# Placa_Final.net
KiCad netlist of a schematic drawn in EAGLE
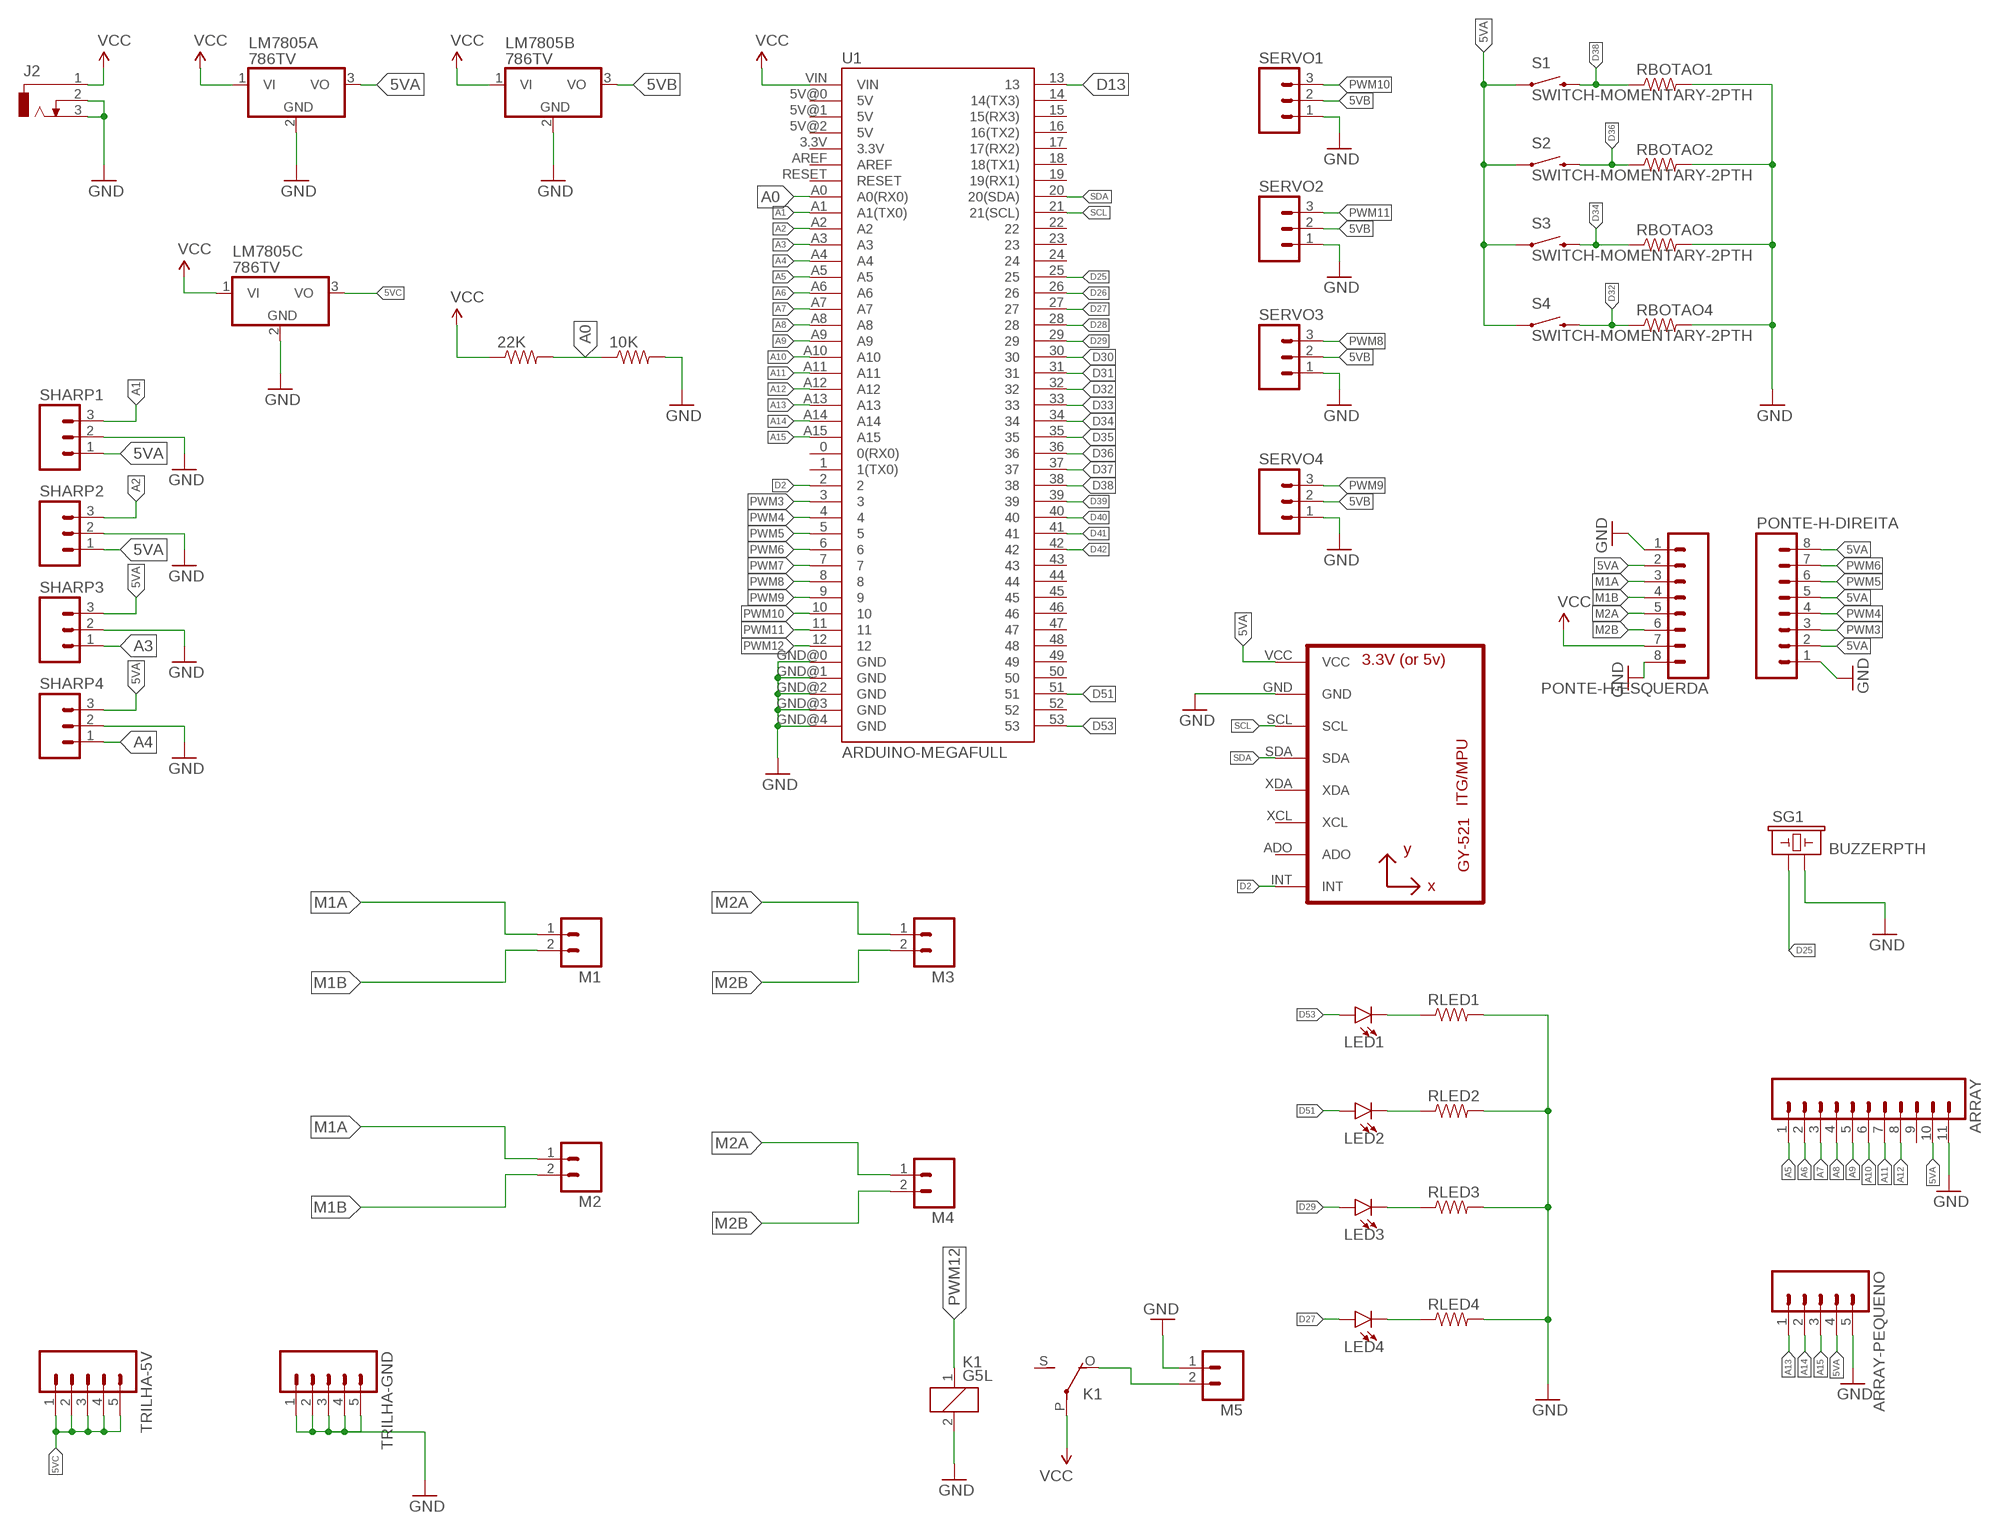
[diagram p0: schematic, sheet 1]
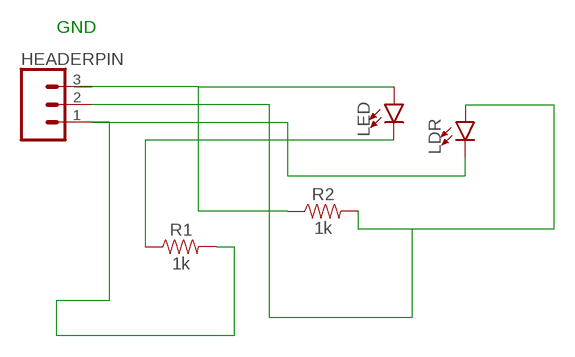
[diagram p1: schematic, sheet 2]
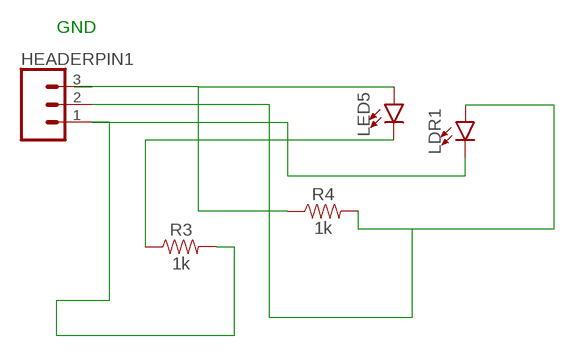
[diagram p2: schematic, sheet 3]
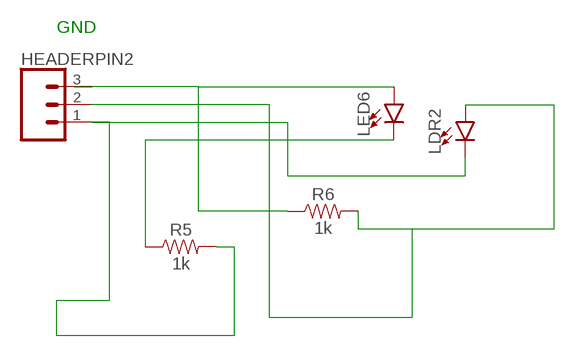
[diagram p3: schematic, sheet 4]
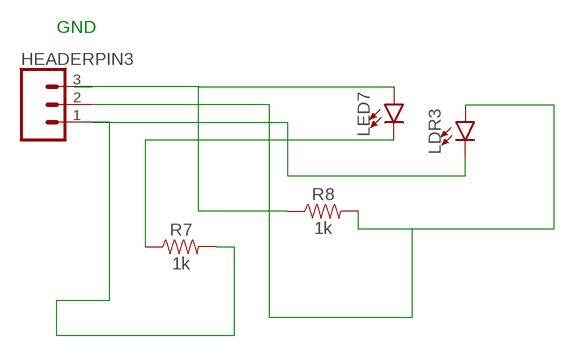
[diagram p4: schematic, sheet 5]
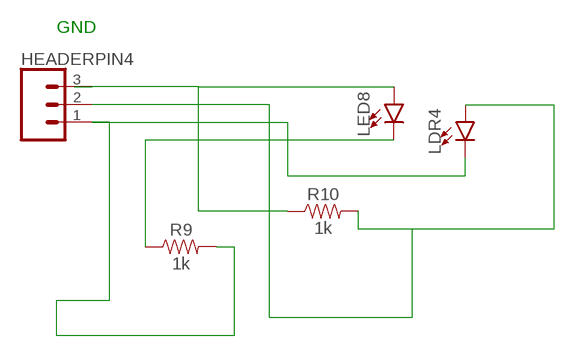
[diagram p5: schematic, sheet 6]
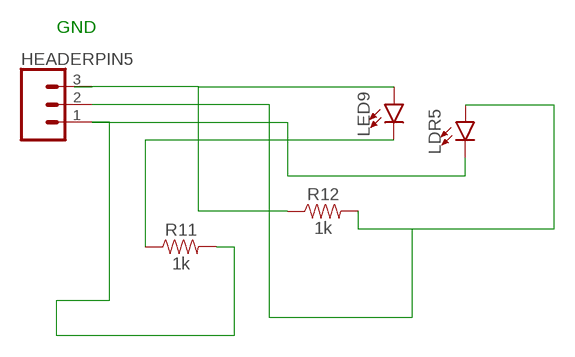
[diagram p6: schematic, sheet 7]
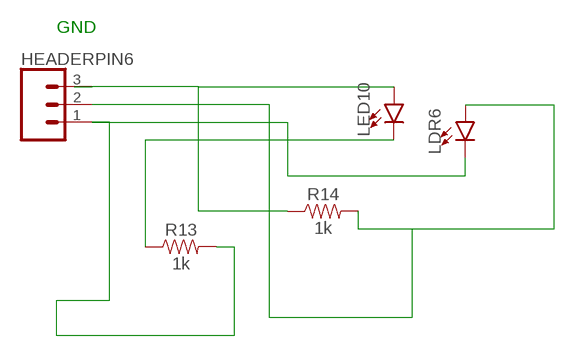
[diagram p7: schematic, sheet 8]
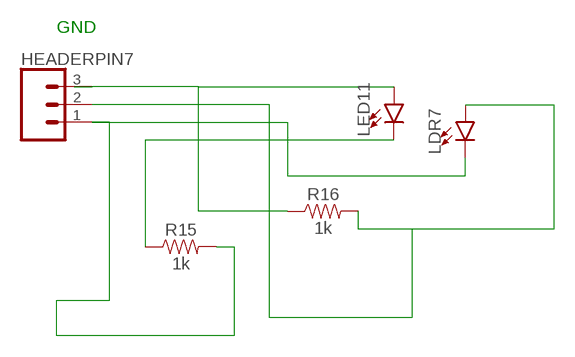
[diagram p8: schematic, sheet 9]
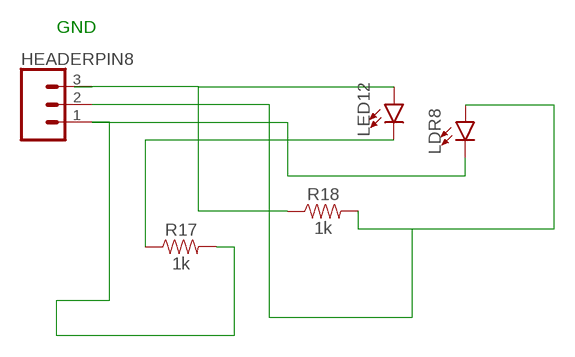
[diagram p9: schematic, sheet 10]

(export (version "E")
  (design (tool "Eeschema 10.0.6"))
  (components
    (comp (ref "HEADERPIN5")
      (value "CONN_03")
      (footprint "eagle-import:1X03")
      (libsource (lib "eagle-import") (part "CONN_03"))
    )
    (comp (ref "LDR5")
      (value "LED5MM")
      (footprint "eagle-import:LED_5MM")
      (libsource (lib "eagle-import") (part "LED5MM"))
    )
    (comp (ref "LED9")
      (value "LED5MM")
      (footprint "eagle-import:LED_5MM")
      (libsource (lib "eagle-import") (part "LED5MM"))
    )
    (comp (ref "R11")
      (value "1k")
      (footprint "eagle-import:AXIAL-0.3")
      (libsource (lib "eagle-import") (part "1KOHM-HORIZ-1/4W-5%"))
    )
    (comp (ref "R12")
      (value "1k")
      (footprint "eagle-import:AXIAL-0.3")
      (libsource (lib "eagle-import") (part "1KOHM-HORIZ-1/4W-5%"))
    )
    (comp (ref "HEADERPIN2")
      (value "CONN_03")
      (footprint "eagle-import:1X03")
      (libsource (lib "eagle-import") (part "CONN_03"))
    )
    (comp (ref "LDR2")
      (value "LED5MM")
      (footprint "eagle-import:LED_5MM")
      (libsource (lib "eagle-import") (part "LED5MM"))
    )
    (comp (ref "LED6")
      (value "LED5MM")
      (footprint "eagle-import:LED_5MM")
      (libsource (lib "eagle-import") (part "LED5MM"))
    )
    (comp (ref "R5")
      (value "1k")
      (footprint "eagle-import:AXIAL-0.3")
      (libsource (lib "eagle-import") (part "1KOHM-HORIZ-1/4W-5%"))
    )
    (comp (ref "R6")
      (value "1k")
      (footprint "eagle-import:AXIAL-0.3")
      (libsource (lib "eagle-import") (part "1KOHM-HORIZ-1/4W-5%"))
    )
    (comp (ref "HEADERPIN")
      (value "CONN_03")
      (footprint "eagle-import:1X03")
      (libsource (lib "eagle-import") (part "CONN_03"))
    )
    (comp (ref "LDR")
      (value "LED5MM")
      (footprint "eagle-import:LED_5MM")
      (libsource (lib "eagle-import") (part "LED5MM"))
    )
    (comp (ref "LED")
      (value "LED5MM")
      (footprint "eagle-import:LED_5MM")
      (libsource (lib "eagle-import") (part "LED5MM"))
    )
    (comp (ref "R1")
      (value "1k")
      (footprint "eagle-import:AXIAL-0.3")
      (libsource (lib "eagle-import") (part "1KOHM-HORIZ-1/4W-5%"))
    )
    (comp (ref "R2")
      (value "1k")
      (footprint "eagle-import:AXIAL-0.3")
      (libsource (lib "eagle-import") (part "1KOHM-HORIZ-1/4W-5%"))
    )
    (comp (ref "HEADERPIN3")
      (value "CONN_03")
      (footprint "eagle-import:1X03")
      (libsource (lib "eagle-import") (part "CONN_03"))
    )
    (comp (ref "LDR3")
      (value "LED5MM")
      (footprint "eagle-import:LED_5MM")
      (libsource (lib "eagle-import") (part "LED5MM"))
    )
    (comp (ref "LED7")
      (value "LED5MM")
      (footprint "eagle-import:LED_5MM")
      (libsource (lib "eagle-import") (part "LED5MM"))
    )
    (comp (ref "R7")
      (value "1k")
      (footprint "eagle-import:AXIAL-0.3")
      (libsource (lib "eagle-import") (part "1KOHM-HORIZ-1/4W-5%"))
    )
    (comp (ref "R8")
      (value "1k")
      (footprint "eagle-import:AXIAL-0.3")
      (libsource (lib "eagle-import") (part "1KOHM-HORIZ-1/4W-5%"))
    )
    (comp (ref "HEADERPIN8")
      (value "CONN_03")
      (footprint "eagle-import:1X03")
      (libsource (lib "eagle-import") (part "CONN_03"))
    )
    (comp (ref "LDR8")
      (value "LED5MM")
      (footprint "eagle-import:LED_5MM")
      (libsource (lib "eagle-import") (part "LED5MM"))
    )
    (comp (ref "LED12")
      (value "LED5MM")
      (footprint "eagle-import:LED_5MM")
      (libsource (lib "eagle-import") (part "LED5MM"))
    )
    (comp (ref "R17")
      (value "1k")
      (footprint "eagle-import:AXIAL-0.3")
      (libsource (lib "eagle-import") (part "1KOHM-HORIZ-1/4W-5%"))
    )
    (comp (ref "R18")
      (value "1k")
      (footprint "eagle-import:AXIAL-0.3")
      (libsource (lib "eagle-import") (part "1KOHM-HORIZ-1/4W-5%"))
    )
    (comp (ref "HEADERPIN6")
      (value "CONN_03")
      (footprint "eagle-import:1X03")
      (libsource (lib "eagle-import") (part "CONN_03"))
    )
    (comp (ref "LDR6")
      (value "LED5MM")
      (footprint "eagle-import:LED_5MM")
      (libsource (lib "eagle-import") (part "LED5MM"))
    )
    (comp (ref "LED10")
      (value "LED5MM")
      (footprint "eagle-import:LED_5MM")
      (libsource (lib "eagle-import") (part "LED5MM"))
    )
    (comp (ref "R13")
      (value "1k")
      (footprint "eagle-import:AXIAL-0.3")
      (libsource (lib "eagle-import") (part "1KOHM-HORIZ-1/4W-5%"))
    )
    (comp (ref "R14")
      (value "1k")
      (footprint "eagle-import:AXIAL-0.3")
      (libsource (lib "eagle-import") (part "1KOHM-HORIZ-1/4W-5%"))
    )
    (comp (ref "HEADERPIN7")
      (value "CONN_03")
      (footprint "eagle-import:1X03")
      (libsource (lib "eagle-import") (part "CONN_03"))
    )
    (comp (ref "LDR7")
      (value "LED5MM")
      (footprint "eagle-import:LED_5MM")
      (libsource (lib "eagle-import") (part "LED5MM"))
    )
    (comp (ref "LED11")
      (value "LED5MM")
      (footprint "eagle-import:LED_5MM")
      (libsource (lib "eagle-import") (part "LED5MM"))
    )
    (comp (ref "R15")
      (value "1k")
      (footprint "eagle-import:AXIAL-0.3")
      (libsource (lib "eagle-import") (part "1KOHM-HORIZ-1/4W-5%"))
    )
    (comp (ref "R16")
      (value "1k")
      (footprint "eagle-import:AXIAL-0.3")
      (libsource (lib "eagle-import") (part "1KOHM-HORIZ-1/4W-5%"))
    )
    (comp (ref "HEADERPIN4")
      (value "CONN_03")
      (footprint "eagle-import:1X03")
      (libsource (lib "eagle-import") (part "CONN_03"))
    )
    (comp (ref "LDR4")
      (value "LED5MM")
      (footprint "eagle-import:LED_5MM")
      (libsource (lib "eagle-import") (part "LED5MM"))
    )
    (comp (ref "LED8")
      (value "LED5MM")
      (footprint "eagle-import:LED_5MM")
      (libsource (lib "eagle-import") (part "LED5MM"))
    )
    (comp (ref "R9")
      (value "1k")
      (footprint "eagle-import:AXIAL-0.3")
      (libsource (lib "eagle-import") (part "1KOHM-HORIZ-1/4W-5%"))
    )
    (comp (ref "R10")
      (value "1k")
      (footprint "eagle-import:AXIAL-0.3")
      (libsource (lib "eagle-import") (part "1KOHM-HORIZ-1/4W-5%"))
    )
    (comp (ref "10K")
      (value "RESISTOREZ")
      (footprint "eagle-import:AXIAL-0.3EZ")
      (libsource (lib "eagle-import") (part "RESISTOREZ"))
    )
    (comp (ref "22K")
      (value "RESISTOREZ")
      (footprint "eagle-import:AXIAL-0.3EZ")
      (libsource (lib "eagle-import") (part "RESISTOREZ"))
    )
    (comp (ref "ARRAY")
      (value "M11POGOPIN_HOLES_ONLY")
      (footprint "eagle-import:1X11_HOLES_ONLY")
      (libsource (lib "eagle-import") (part "M11POGOPIN_HOLES_ONLY"))
    )
    (comp (ref "ARRAY-PEQUENO")
      (value "M05PTH")
      (footprint "eagle-import:1X05")
      (libsource (lib "eagle-import") (part "M05PTH"))
    )
    (comp (ref "J2")
      (value "DCJ0303")
      (footprint "eagle-import:DCJ0303")
      (libsource (lib "eagle-import") (part "DCJ0303"))
    )
    (comp (ref "K1")
      (value "G5L")
      (footprint "eagle-import:G5LE")
      (libsource (lib "eagle-import") (part "G5L"))
    )
    (comp (ref "LED1")
      (value "LED5MM")
      (footprint "eagle-import:LED_5MM")
      (libsource (lib "eagle-import") (part "LED5MM"))
    )
    (comp (ref "LED2")
      (value "LED5MM")
      (footprint "eagle-import:LED_5MM")
      (libsource (lib "eagle-import") (part "LED5MM"))
    )
    (comp (ref "LED3")
      (value "LED5MM")
      (footprint "eagle-import:LED_5MM")
      (libsource (lib "eagle-import") (part "LED5MM"))
    )
    (comp (ref "LED4")
      (value "LED5MM")
      (footprint "eagle-import:LED_5MM")
      (libsource (lib "eagle-import") (part "LED5MM"))
    )
    (comp (ref "LM7805A")
      (value "786TV")
      (footprint "eagle-import:TO220V")
      (libsource (lib "eagle-import") (part "78TV6"))
    )
    (comp (ref "LM7805B")
      (value "786TV")
      (footprint "eagle-import:TO220V")
      (libsource (lib "eagle-import") (part "78TV6"))
    )
    (comp (ref "LM7805C")
      (value "786TV")
      (footprint "eagle-import:TO220V")
      (libsource (lib "eagle-import") (part "78TV6"))
    )
    (comp (ref "M1")
      (value "M02JST-PTH-VERT")
      (footprint "eagle-import:JST-2-PTH-VERT")
      (libsource (lib "eagle-import") (part "M02JST-PTH-VERT"))
    )
    (comp (ref "M2")
      (value "M02JST-PTH-VERT")
      (footprint "eagle-import:JST-2-PTH-VERT")
      (libsource (lib "eagle-import") (part "M02JST-PTH-VERT"))
    )
    (comp (ref "M3")
      (value "M02JST-PTH-VERT")
      (footprint "eagle-import:JST-2-PTH-VERT")
      (libsource (lib "eagle-import") (part "M02JST-PTH-VERT"))
    )
    (comp (ref "M4")
      (value "M02JST-PTH-VERT")
      (footprint "eagle-import:JST-2-PTH-VERT")
      (libsource (lib "eagle-import") (part "M02JST-PTH-VERT"))
    )
    (comp (ref "M5")
      (value "M02JST-PTH-VERT")
      (footprint "eagle-import:JST-2-PTH-VERT")
      (libsource (lib "eagle-import") (part "M02JST-PTH-VERT"))
    )
    (comp (ref "PONTE-H-DIREITA")
      (value "M08NO_SILK")
      (footprint "eagle-import:1X08_PIN1_NO_SILK")
      (libsource (lib "eagle-import") (part "M08NO_SILK"))
    )
    (comp (ref "PONTE-H-ESQUERDA")
      (value "M08NO_SILK")
      (footprint "eagle-import:1X08_PIN1_NO_SILK")
      (libsource (lib "eagle-import") (part "M08NO_SILK"))
    )
    (comp (ref "RBOTAO1")
      (value "RESISTOREZ")
      (footprint "eagle-import:AXIAL-0.3EZ")
      (libsource (lib "eagle-import") (part "RESISTOREZ"))
    )
    (comp (ref "RBOTAO2")
      (value "RESISTOREZ")
      (footprint "eagle-import:AXIAL-0.3EZ")
      (libsource (lib "eagle-import") (part "RESISTOREZ"))
    )
    (comp (ref "RBOTAO3")
      (value "RESISTOREZ")
      (footprint "eagle-import:AXIAL-0.3EZ")
      (libsource (lib "eagle-import") (part "RESISTOREZ"))
    )
    (comp (ref "RBOTAO4")
      (value "RESISTOREZ")
      (footprint "eagle-import:AXIAL-0.3EZ")
      (libsource (lib "eagle-import") (part "RESISTOREZ"))
    )
    (comp (ref "RLED1")
      (value "RESISTOREZ")
      (footprint "eagle-import:AXIAL-0.3EZ")
      (libsource (lib "eagle-import") (part "RESISTOREZ"))
    )
    (comp (ref "RLED2")
      (value "RESISTOREZ")
      (footprint "eagle-import:AXIAL-0.3EZ")
      (libsource (lib "eagle-import") (part "RESISTOREZ"))
    )
    (comp (ref "RLED3")
      (value "RESISTOREZ")
      (footprint "eagle-import:AXIAL-0.3EZ")
      (libsource (lib "eagle-import") (part "RESISTOREZ"))
    )
    (comp (ref "RLED4")
      (value "RESISTOREZ")
      (footprint "eagle-import:AXIAL-0.3EZ")
      (libsource (lib "eagle-import") (part "RESISTOREZ"))
    )
    (comp (ref "S1")
      (value "SWITCH-MOMENTARY-2PTH")
      (footprint "eagle-import:TACTILE-PTH")
      (libsource (lib "eagle-import") (part "SWITCH-MOMENTARY-2PTH"))
    )
    (comp (ref "S2")
      (value "SWITCH-MOMENTARY-2PTH")
      (footprint "eagle-import:TACTILE-PTH")
      (libsource (lib "eagle-import") (part "SWITCH-MOMENTARY-2PTH"))
    )
    (comp (ref "S3")
      (value "SWITCH-MOMENTARY-2PTH")
      (footprint "eagle-import:TACTILE-PTH")
      (libsource (lib "eagle-import") (part "SWITCH-MOMENTARY-2PTH"))
    )
    (comp (ref "S4")
      (value "SWITCH-MOMENTARY-2PTH")
      (footprint "eagle-import:TACTILE-PTH")
      (libsource (lib "eagle-import") (part "SWITCH-MOMENTARY-2PTH"))
    )
    (comp (ref "SERVO1")
      (value "M03LONGPADS")
      (footprint "eagle-import:1X03_LONGPADS@1")
      (libsource (lib "eagle-import") (part "M03LONGPADS"))
    )
    (comp (ref "SERVO2")
      (value "M03LONGPADS")
      (footprint "eagle-import:1X03_LONGPADS@1")
      (libsource (lib "eagle-import") (part "M03LONGPADS"))
    )
    (comp (ref "SERVO3")
      (value "M03LONGPADS")
      (footprint "eagle-import:1X03_LONGPADS@1")
      (libsource (lib "eagle-import") (part "M03LONGPADS"))
    )
    (comp (ref "SERVO4")
      (value "M03LONGPADS")
      (footprint "eagle-import:1X03_LONGPADS@1")
      (libsource (lib "eagle-import") (part "M03LONGPADS"))
    )
    (comp (ref "SG1")
      (value "BUZZERPTH")
      (footprint "eagle-import:BUZZER-12MM")
      (libsource (lib "eagle-import") (part "BUZZERPTH"))
    )
    (comp (ref "SHARP1")
      (value "M03LONGPADS")
      (footprint "eagle-import:1X03_LONGPADS@1")
      (libsource (lib "eagle-import") (part "M03LONGPADS"))
    )
    (comp (ref "SHARP2")
      (value "M03LONGPADS")
      (footprint "eagle-import:1X03_LONGPADS@1")
      (libsource (lib "eagle-import") (part "M03LONGPADS"))
    )
    (comp (ref "SHARP3")
      (value "M03LONGPADS")
      (footprint "eagle-import:1X03_LONGPADS@1")
      (libsource (lib "eagle-import") (part "M03LONGPADS"))
    )
    (comp (ref "SHARP4")
      (value "M03LONGPADS")
      (footprint "eagle-import:1X03_LONGPADS@1")
      (libsource (lib "eagle-import") (part "M03LONGPADS"))
    )
    (comp (ref "TRILHA-5V")
      (value "M05PTH")
      (footprint "eagle-import:1X05")
      (libsource (lib "eagle-import") (part "M05PTH"))
    )
    (comp (ref "TRILHA-GND")
      (value "M05PTH")
      (footprint "eagle-import:1X05")
      (libsource (lib "eagle-import") (part "M05PTH"))
    )
    (comp (ref "U1")
      (value "ARDUINO-MEGAFULL")
      (footprint "eagle-import:ARDUINO_MEGA")
      (libsource (lib "eagle-import") (part "ARDUINO-MEGAFULL"))
    )
    (comp (ref "U2")
      (value "GY-521MPU6050")
      (footprint "eagle-import:GY-521")
      (libsource (lib "eagle-import") (part "GY-521MPU6050"))
    )
    (comp (ref "HEADERPIN1")
      (value "CONN_03")
      (footprint "eagle-import:1X03")
      (libsource (lib "eagle-import") (part "CONN_03"))
    )
    (comp (ref "LDR1")
      (value "LED5MM")
      (footprint "eagle-import:LED_5MM")
      (libsource (lib "eagle-import") (part "LED5MM"))
    )
    (comp (ref "LED5")
      (value "LED5MM")
      (footprint "eagle-import:LED_5MM")
      (libsource (lib "eagle-import") (part "LED5MM"))
    )
    (comp (ref "R3")
      (value "1k")
      (footprint "eagle-import:AXIAL-0.3")
      (libsource (lib "eagle-import") (part "1KOHM-HORIZ-1/4W-5%"))
    )
    (comp (ref "R4")
      (value "1k")
      (footprint "eagle-import:AXIAL-0.3")
      (libsource (lib "eagle-import") (part "1KOHM-HORIZ-1/4W-5%"))
    )
  )
  (nets
    (net (code "1") (name "5VA") (class "Default")
      (node (ref "ARRAY") (pin "10") (pinfunction "10_10") (pintype "passive"))
      (node (ref "ARRAY-PEQUENO") (pin "4") (pinfunction "4_4") (pintype "passive"))
      (node (ref "LM7805A") (pin "3") (pinfunction "VO_3") (pintype "passive"))
      (node (ref "PONTE-H-DIREITA") (pin "2") (pinfunction "2_2") (pintype "passive"))
      (node (ref "PONTE-H-DIREITA") (pin "5") (pinfunction "5_5") (pintype "passive"))
      (node (ref "PONTE-H-DIREITA") (pin "8") (pinfunction "8_8") (pintype "passive"))
      (node (ref "PONTE-H-ESQUERDA") (pin "2") (pinfunction "2_2") (pintype "passive"))
      (node (ref "S1") (pin "1") (pinfunction "1_1") (pintype "passive"))
      (node (ref "S2") (pin "1") (pinfunction "1_1") (pintype "passive"))
      (node (ref "S3") (pin "1") (pinfunction "1_1") (pintype "passive"))
      (node (ref "S4") (pin "1") (pinfunction "1_1") (pintype "passive"))
      (node (ref "SHARP1") (pin "1") (pinfunction "1_1") (pintype "passive"))
      (node (ref "SHARP2") (pin "1") (pinfunction "1_1") (pintype "passive"))
      (node (ref "SHARP3") (pin "3") (pinfunction "3_3") (pintype "passive"))
      (node (ref "SHARP4") (pin "3") (pinfunction "3_3") (pintype "passive"))
      (node (ref "U2") (pin "VCC") (pinfunction "VCC_VCC") (pintype "bidirectional"))
    )
    (net (code "2") (name "5VB") (class "Default")
      (node (ref "LM7805B") (pin "3") (pinfunction "VO_3") (pintype "passive"))
      (node (ref "SERVO1") (pin "2") (pinfunction "2_2") (pintype "passive"))
      (node (ref "SERVO2") (pin "2") (pinfunction "2_2") (pintype "passive"))
      (node (ref "SERVO3") (pin "2") (pinfunction "2_2") (pintype "passive"))
      (node (ref "SERVO4") (pin "2") (pinfunction "2_2") (pintype "passive"))
    )
    (net (code "3") (name "5VC") (class "Default")
      (node (ref "LM7805C") (pin "3") (pinfunction "VO_3") (pintype "passive"))
      (node (ref "TRILHA-5V") (pin "1") (pinfunction "1_1") (pintype "passive"))
      (node (ref "TRILHA-5V") (pin "2") (pinfunction "2_2") (pintype "passive"))
      (node (ref "TRILHA-5V") (pin "3") (pinfunction "3_3") (pintype "passive"))
      (node (ref "TRILHA-5V") (pin "4") (pinfunction "4_4") (pintype "passive"))
      (node (ref "TRILHA-5V") (pin "5") (pinfunction "5_5") (pintype "passive"))
    )
    (net (code "4") (name "A0") (class "Default")
      (node (ref "10K") (pin "P$1") (pinfunction "1_P$1") (pintype "passive"))
      (node (ref "22K") (pin "P$2") (pinfunction "2_P$2") (pintype "passive"))
      (node (ref "U1") (pin "A0") (pinfunction "A0(RX0)_A0") (pintype "bidirectional"))
    )
    (net (code "5") (name "A1") (class "Default")
      (node (ref "SHARP1") (pin "3") (pinfunction "3_3") (pintype "passive"))
      (node (ref "U1") (pin "A1") (pinfunction "A1(TX0)_A1") (pintype "bidirectional"))
    )
    (net (code "6") (name "A2") (class "Default")
      (node (ref "SHARP2") (pin "3") (pinfunction "3_3") (pintype "passive"))
      (node (ref "U1") (pin "A2") (pinfunction "A2_A2") (pintype "bidirectional"))
    )
    (net (code "7") (name "A3") (class "Default")
      (node (ref "SHARP3") (pin "1") (pinfunction "1_1") (pintype "passive"))
      (node (ref "U1") (pin "A3") (pinfunction "A3_A3") (pintype "bidirectional"))
    )
    (net (code "8") (name "A4") (class "Default")
      (node (ref "SHARP4") (pin "1") (pinfunction "1_1") (pintype "passive"))
      (node (ref "U1") (pin "A4") (pinfunction "A4_A4") (pintype "bidirectional"))
    )
    (net (code "9") (name "A5") (class "Default")
      (node (ref "ARRAY") (pin "1") (pinfunction "1_1") (pintype "passive"))
      (node (ref "U1") (pin "A5") (pinfunction "A5_A5") (pintype "bidirectional"))
    )
    (net (code "10") (name "A6") (class "Default")
      (node (ref "ARRAY") (pin "2") (pinfunction "2_2") (pintype "passive"))
      (node (ref "U1") (pin "A6") (pinfunction "A6_A6") (pintype "bidirectional"))
    )
    (net (code "11") (name "A7") (class "Default")
      (node (ref "ARRAY") (pin "3") (pinfunction "3_3") (pintype "passive"))
      (node (ref "U1") (pin "A7") (pinfunction "A7_A7") (pintype "bidirectional"))
    )
    (net (code "12") (name "A8") (class "Default")
      (node (ref "ARRAY") (pin "4") (pinfunction "4_4") (pintype "passive"))
      (node (ref "U1") (pin "A8") (pinfunction "A8_A8") (pintype "bidirectional"))
    )
    (net (code "13") (name "A9") (class "Default")
      (node (ref "ARRAY") (pin "5") (pinfunction "5_5") (pintype "passive"))
      (node (ref "U1") (pin "A9") (pinfunction "A9_A9") (pintype "bidirectional"))
    )
    (net (code "14") (name "A10") (class "Default")
      (node (ref "ARRAY") (pin "6") (pinfunction "6_6") (pintype "passive"))
      (node (ref "U1") (pin "A10") (pinfunction "A10_A10") (pintype "bidirectional"))
    )
    (net (code "15") (name "A11") (class "Default")
      (node (ref "ARRAY") (pin "7") (pinfunction "7_7") (pintype "passive"))
      (node (ref "U1") (pin "A11") (pinfunction "A11_A11") (pintype "bidirectional"))
    )
    (net (code "16") (name "A12") (class "Default")
      (node (ref "ARRAY") (pin "8") (pinfunction "8_8") (pintype "passive"))
      (node (ref "U1") (pin "A12") (pinfunction "A12_A12") (pintype "bidirectional"))
    )
    (net (code "17") (name "A13") (class "Default")
      (node (ref "ARRAY-PEQUENO") (pin "1") (pinfunction "1_1") (pintype "passive"))
      (node (ref "U1") (pin "A13") (pinfunction "A13_A13") (pintype "bidirectional"))
    )
    (net (code "18") (name "A14") (class "Default")
      (node (ref "ARRAY-PEQUENO") (pin "2") (pinfunction "2_2") (pintype "passive"))
      (node (ref "U1") (pin "A14") (pinfunction "A14_A14") (pintype "bidirectional"))
    )
    (net (code "19") (name "A15") (class "Default")
      (node (ref "ARRAY-PEQUENO") (pin "3") (pinfunction "3_3") (pintype "passive"))
      (node (ref "U1") (pin "A15") (pinfunction "A15_A15") (pintype "bidirectional"))
    )
    (net (code "20") (name "D2") (class "Default")
      (node (ref "U1") (pin "2") (pinfunction "2_2") (pintype "bidirectional"))
      (node (ref "U2") (pin "INT") (pinfunction "INT_INT") (pintype "bidirectional"))
    )
    (net (code "21") (name "D13") (class "Default")
      (node (ref "U1") (pin "13") (pinfunction "13_13") (pintype "bidirectional"))
    )
    (net (code "22") (name "D25") (class "Default")
      (node (ref "SG1") (pin "+") (pinfunction "1_+") (pintype "passive"))
      (node (ref "U1") (pin "25") (pinfunction "25_25") (pintype "bidirectional"))
    )
    (net (code "23") (name "D26") (class "Default")
      (node (ref "U1") (pin "26") (pinfunction "26_26") (pintype "bidirectional"))
    )
    (net (code "24") (name "D27") (class "Default")
      (node (ref "LED4") (pin "A") (pinfunction "A_A") (pintype "passive"))
      (node (ref "U1") (pin "27") (pinfunction "27_27") (pintype "bidirectional"))
    )
    (net (code "25") (name "D28") (class "Default")
      (node (ref "U1") (pin "28") (pinfunction "28_28") (pintype "bidirectional"))
    )
    (net (code "26") (name "D29") (class "Default")
      (node (ref "LED3") (pin "A") (pinfunction "A_A") (pintype "passive"))
      (node (ref "U1") (pin "29") (pinfunction "29_29") (pintype "bidirectional"))
    )
    (net (code "27") (name "D30") (class "Default")
      (node (ref "U1") (pin "30") (pinfunction "30_30") (pintype "bidirectional"))
    )
    (net (code "28") (name "D31") (class "Default")
      (node (ref "U1") (pin "31") (pinfunction "31_31") (pintype "bidirectional"))
    )
    (net (code "29") (name "D32") (class "Default")
      (node (ref "RBOTAO4") (pin "P$1") (pinfunction "1_P$1") (pintype "passive"))
      (node (ref "S4") (pin "3") (pinfunction "2_3") (pintype "passive"))
      (node (ref "U1") (pin "32") (pinfunction "32_32") (pintype "bidirectional"))
    )
    (net (code "30") (name "D33") (class "Default")
      (node (ref "U1") (pin "33") (pinfunction "33_33") (pintype "bidirectional"))
    )
    (net (code "31") (name "D34") (class "Default")
      (node (ref "RBOTAO3") (pin "P$1") (pinfunction "1_P$1") (pintype "passive"))
      (node (ref "S3") (pin "3") (pinfunction "2_3") (pintype "passive"))
      (node (ref "U1") (pin "34") (pinfunction "34_34") (pintype "bidirectional"))
    )
    (net (code "32") (name "D35") (class "Default")
      (node (ref "U1") (pin "35") (pinfunction "35_35") (pintype "bidirectional"))
    )
    (net (code "33") (name "D36") (class "Default")
      (node (ref "RBOTAO2") (pin "P$1") (pinfunction "1_P$1") (pintype "passive"))
      (node (ref "S2") (pin "3") (pinfunction "2_3") (pintype "passive"))
      (node (ref "U1") (pin "36") (pinfunction "36_36") (pintype "bidirectional"))
    )
    (net (code "34") (name "D37") (class "Default")
      (node (ref "U1") (pin "37") (pinfunction "37_37") (pintype "bidirectional"))
    )
    (net (code "35") (name "D38") (class "Default")
      (node (ref "RBOTAO1") (pin "P$1") (pinfunction "1_P$1") (pintype "passive"))
      (node (ref "S1") (pin "3") (pinfunction "2_3") (pintype "passive"))
      (node (ref "U1") (pin "38") (pinfunction "38_38") (pintype "bidirectional"))
    )
    (net (code "36") (name "D39") (class "Default")
      (node (ref "U1") (pin "39") (pinfunction "39_39") (pintype "bidirectional"))
    )
    (net (code "37") (name "D40") (class "Default")
      (node (ref "U1") (pin "40") (pinfunction "40_40") (pintype "bidirectional"))
    )
    (net (code "38") (name "D41") (class "Default")
      (node (ref "U1") (pin "41") (pinfunction "41_41") (pintype "bidirectional"))
    )
    (net (code "39") (name "D42") (class "Default")
      (node (ref "U1") (pin "42") (pinfunction "42_42") (pintype "bidirectional"))
    )
    (net (code "40") (name "D51") (class "Default")
      (node (ref "LED2") (pin "A") (pinfunction "A_A") (pintype "passive"))
      (node (ref "U1") (pin "51") (pinfunction "51_51") (pintype "bidirectional"))
    )
    (net (code "41") (name "D53") (class "Default")
      (node (ref "LED1") (pin "A") (pinfunction "A_A") (pintype "passive"))
      (node (ref "U1") (pin "53") (pinfunction "53_53") (pintype "bidirectional"))
    )
    (net (code "42") (name "GND") (class "Default")
      (node (ref "10K") (pin "P$2") (pinfunction "2_P$2") (pintype "passive"))
      (node (ref "ARRAY") (pin "11") (pinfunction "11_11") (pintype "passive"))
      (node (ref "ARRAY-PEQUENO") (pin "5") (pinfunction "5_5") (pintype "passive"))
      (node (ref "J2") (pin "2") (pinfunction "2_2") (pintype "passive"))
      (node (ref "J2") (pin "3") (pinfunction "3_3") (pintype "passive"))
      (node (ref "K1") (pin "2") (pinfunction "2_2") (pintype "passive"))
      (node (ref "LM7805A") (pin "2") (pinfunction "GND_2") (pintype "passive"))
      (node (ref "LM7805B") (pin "2") (pinfunction "GND_2") (pintype "passive"))
      (node (ref "LM7805C") (pin "2") (pinfunction "GND_2") (pintype "passive"))
      (node (ref "M5") (pin "1") (pinfunction "1_1") (pintype "passive"))
      (node (ref "PONTE-H-DIREITA") (pin "1") (pinfunction "1_1") (pintype "passive"))
      (node (ref "PONTE-H-ESQUERDA") (pin "1") (pinfunction "1_1") (pintype "passive"))
      (node (ref "PONTE-H-ESQUERDA") (pin "8") (pinfunction "8_8") (pintype "passive"))
      (node (ref "RBOTAO1") (pin "P$2") (pinfunction "2_P$2") (pintype "passive"))
      (node (ref "RBOTAO2") (pin "P$2") (pinfunction "2_P$2") (pintype "passive"))
      (node (ref "RBOTAO3") (pin "P$2") (pinfunction "2_P$2") (pintype "passive"))
      (node (ref "RBOTAO4") (pin "P$2") (pinfunction "2_P$2") (pintype "passive"))
      (node (ref "RLED1") (pin "P$2") (pinfunction "2_P$2") (pintype "passive"))
      (node (ref "RLED2") (pin "P$2") (pinfunction "2_P$2") (pintype "passive"))
      (node (ref "RLED3") (pin "P$2") (pinfunction "2_P$2") (pintype "passive"))
      (node (ref "RLED4") (pin "P$2") (pinfunction "2_P$2") (pintype "passive"))
      (node (ref "SERVO1") (pin "1") (pinfunction "1_1") (pintype "passive"))
      (node (ref "SERVO2") (pin "1") (pinfunction "1_1") (pintype "passive"))
      (node (ref "SERVO3") (pin "1") (pinfunction "1_1") (pintype "passive"))
      (node (ref "SERVO4") (pin "1") (pinfunction "1_1") (pintype "passive"))
      (node (ref "SG1") (pin "-") (pinfunction "2_-") (pintype "passive"))
      (node (ref "SHARP1") (pin "2") (pinfunction "2_2") (pintype "passive"))
      (node (ref "SHARP2") (pin "2") (pinfunction "2_2") (pintype "passive"))
      (node (ref "SHARP3") (pin "2") (pinfunction "2_2") (pintype "passive"))
      (node (ref "SHARP4") (pin "2") (pinfunction "2_2") (pintype "passive"))
      (node (ref "TRILHA-GND") (pin "1") (pinfunction "1_1") (pintype "passive"))
      (node (ref "TRILHA-GND") (pin "2") (pinfunction "2_2") (pintype "passive"))
      (node (ref "TRILHA-GND") (pin "3") (pinfunction "3_3") (pintype "passive"))
      (node (ref "TRILHA-GND") (pin "4") (pinfunction "4_4") (pintype "passive"))
      (node (ref "TRILHA-GND") (pin "5") (pinfunction "5_5") (pintype "passive"))
      (node (ref "U1") (pin "GND@0") (pinfunction "GND_GND@0") (pintype "bidirectional"))
      (node (ref "U1") (pin "GND@1") (pinfunction "GND_GND@1") (pintype "bidirectional"))
      (node (ref "U1") (pin "GND@2") (pinfunction "GND_GND@2") (pintype "bidirectional"))
      (node (ref "U1") (pin "GND@3") (pinfunction "GND_GND@3") (pintype "bidirectional"))
      (node (ref "U1") (pin "GND@4") (pinfunction "GND_GND@4") (pintype "bidirectional"))
      (node (ref "U2") (pin "GND") (pinfunction "GND_GND") (pintype "bidirectional"))
    )
    (net (code "43") (name "M1A") (class "Default")
      (node (ref "M1") (pin "1") (pinfunction "1_1") (pintype "passive"))
      (node (ref "M2") (pin "1") (pinfunction "1_1") (pintype "passive"))
      (node (ref "PONTE-H-ESQUERDA") (pin "3") (pinfunction "3_3") (pintype "passive"))
    )
    (net (code "44") (name "M1B") (class "Default")
      (node (ref "M1") (pin "2") (pinfunction "2_2") (pintype "passive"))
      (node (ref "M2") (pin "2") (pinfunction "2_2") (pintype "passive"))
      (node (ref "PONTE-H-ESQUERDA") (pin "4") (pinfunction "4_4") (pintype "passive"))
    )
    (net (code "45") (name "M2A") (class "Default")
      (node (ref "M3") (pin "1") (pinfunction "1_1") (pintype "passive"))
      (node (ref "M4") (pin "1") (pinfunction "1_1") (pintype "passive"))
      (node (ref "PONTE-H-ESQUERDA") (pin "5") (pinfunction "5_5") (pintype "passive"))
    )
    (net (code "46") (name "M2B") (class "Default")
      (node (ref "M3") (pin "2") (pinfunction "2_2") (pintype "passive"))
      (node (ref "M4") (pin "2") (pinfunction "2_2") (pintype "passive"))
      (node (ref "PONTE-H-ESQUERDA") (pin "6") (pinfunction "6_6") (pintype "passive"))
    )
    (net (code "47") (name "Net-(K1-PadO)") (class "Default")
      (node (ref "K1") (pin "O") (pinfunction "O_O") (pintype "passive"))
      (node (ref "M5") (pin "2") (pinfunction "2_2") (pintype "passive"))
    )
    (net (code "48") (name "Net-(LDR-C)") (class "Default")
      (node (ref "HEADERPIN") (pin "1") (pinfunction "1_1") (pintype "passive"))
      (node (ref "LDR") (pin "K") (pinfunction "C_K") (pintype "passive"))
      (node (ref "R1") (pin "P$2") (pinfunction "2_P$2") (pintype "passive"))
    )
    (net (code "49") (name "Net-(LDR1-C)") (class "Default")
      (node (ref "HEADERPIN1") (pin "1") (pinfunction "1_1") (pintype "passive"))
      (node (ref "LDR1") (pin "K") (pinfunction "C_K") (pintype "passive"))
      (node (ref "R3") (pin "P$2") (pinfunction "2_P$2") (pintype "passive"))
    )
    (net (code "50") (name "Net-(LDR2-C)") (class "Default")
      (node (ref "HEADERPIN2") (pin "1") (pinfunction "1_1") (pintype "passive"))
      (node (ref "LDR2") (pin "K") (pinfunction "C_K") (pintype "passive"))
      (node (ref "R5") (pin "P$2") (pinfunction "2_P$2") (pintype "passive"))
    )
    (net (code "51") (name "Net-(LDR3-C)") (class "Default")
      (node (ref "HEADERPIN3") (pin "1") (pinfunction "1_1") (pintype "passive"))
      (node (ref "LDR3") (pin "K") (pinfunction "C_K") (pintype "passive"))
      (node (ref "R7") (pin "P$2") (pinfunction "2_P$2") (pintype "passive"))
    )
    (net (code "52") (name "Net-(LDR4-C)") (class "Default")
      (node (ref "HEADERPIN4") (pin "1") (pinfunction "1_1") (pintype "passive"))
      (node (ref "LDR4") (pin "K") (pinfunction "C_K") (pintype "passive"))
      (node (ref "R9") (pin "P$2") (pinfunction "2_P$2") (pintype "passive"))
    )
    (net (code "53") (name "Net-(LDR5-C)") (class "Default")
      (node (ref "HEADERPIN5") (pin "1") (pinfunction "1_1") (pintype "passive"))
      (node (ref "LDR5") (pin "K") (pinfunction "C_K") (pintype "passive"))
      (node (ref "R11") (pin "P$2") (pinfunction "2_P$2") (pintype "passive"))
    )
    (net (code "54") (name "Net-(LDR6-C)") (class "Default")
      (node (ref "HEADERPIN6") (pin "1") (pinfunction "1_1") (pintype "passive"))
      (node (ref "LDR6") (pin "K") (pinfunction "C_K") (pintype "passive"))
      (node (ref "R13") (pin "P$2") (pinfunction "2_P$2") (pintype "passive"))
    )
    (net (code "55") (name "Net-(LDR7-C)") (class "Default")
      (node (ref "HEADERPIN7") (pin "1") (pinfunction "1_1") (pintype "passive"))
      (node (ref "LDR7") (pin "K") (pinfunction "C_K") (pintype "passive"))
      (node (ref "R15") (pin "P$2") (pinfunction "2_P$2") (pintype "passive"))
    )
    (net (code "56") (name "Net-(LDR8-C)") (class "Default")
      (node (ref "HEADERPIN8") (pin "1") (pinfunction "1_1") (pintype "passive"))
      (node (ref "LDR8") (pin "K") (pinfunction "C_K") (pintype "passive"))
      (node (ref "R17") (pin "P$2") (pinfunction "2_P$2") (pintype "passive"))
    )
    (net (code "57") (name "Net-(LED-C)") (class "Default")
      (node (ref "LED") (pin "K") (pinfunction "C_K") (pintype "passive"))
      (node (ref "R1") (pin "P$1") (pinfunction "1_P$1") (pintype "passive"))
    )
    (net (code "58") (name "Net-(LED1-C)") (class "Default")
      (node (ref "LED1") (pin "K") (pinfunction "C_K") (pintype "passive"))
      (node (ref "RLED1") (pin "P$1") (pinfunction "1_P$1") (pintype "passive"))
    )
    (net (code "59") (name "Net-(LED2-C)") (class "Default")
      (node (ref "LED2") (pin "K") (pinfunction "C_K") (pintype "passive"))
      (node (ref "RLED2") (pin "P$1") (pinfunction "1_P$1") (pintype "passive"))
    )
    (net (code "60") (name "Net-(LED3-C)") (class "Default")
      (node (ref "LED3") (pin "K") (pinfunction "C_K") (pintype "passive"))
      (node (ref "RLED3") (pin "P$1") (pinfunction "1_P$1") (pintype "passive"))
    )
    (net (code "61") (name "Net-(LED4-C)") (class "Default")
      (node (ref "LED4") (pin "K") (pinfunction "C_K") (pintype "passive"))
      (node (ref "RLED4") (pin "P$1") (pinfunction "1_P$1") (pintype "passive"))
    )
    (net (code "62") (name "Net-(LED5-C)") (class "Default")
      (node (ref "LED5") (pin "K") (pinfunction "C_K") (pintype "passive"))
      (node (ref "R3") (pin "P$1") (pinfunction "1_P$1") (pintype "passive"))
    )
    (net (code "63") (name "Net-(LED6-C)") (class "Default")
      (node (ref "LED6") (pin "K") (pinfunction "C_K") (pintype "passive"))
      (node (ref "R5") (pin "P$1") (pinfunction "1_P$1") (pintype "passive"))
    )
    (net (code "64") (name "Net-(LED7-C)") (class "Default")
      (node (ref "LED7") (pin "K") (pinfunction "C_K") (pintype "passive"))
      (node (ref "R7") (pin "P$1") (pinfunction "1_P$1") (pintype "passive"))
    )
    (net (code "65") (name "Net-(LED8-C)") (class "Default")
      (node (ref "LED8") (pin "K") (pinfunction "C_K") (pintype "passive"))
      (node (ref "R9") (pin "P$1") (pinfunction "1_P$1") (pintype "passive"))
    )
    (net (code "66") (name "Net-(LED9-C)") (class "Default")
      (node (ref "LED9") (pin "K") (pinfunction "C_K") (pintype "passive"))
      (node (ref "R11") (pin "P$1") (pinfunction "1_P$1") (pintype "passive"))
    )
    (net (code "67") (name "Net-(LED10-C)") (class "Default")
      (node (ref "LED10") (pin "K") (pinfunction "C_K") (pintype "passive"))
      (node (ref "R13") (pin "P$1") (pinfunction "1_P$1") (pintype "passive"))
    )
    (net (code "68") (name "Net-(LED11-C)") (class "Default")
      (node (ref "LED11") (pin "K") (pinfunction "C_K") (pintype "passive"))
      (node (ref "R15") (pin "P$1") (pinfunction "1_P$1") (pintype "passive"))
    )
    (net (code "69") (name "Net-(LED12-C)") (class "Default")
      (node (ref "LED12") (pin "K") (pinfunction "C_K") (pintype "passive"))
      (node (ref "R17") (pin "P$1") (pinfunction "1_P$1") (pintype "passive"))
    )
    (net (code "70") (name "Net-(R2-1)") (class "Default")
      (node (ref "HEADERPIN") (pin "3") (pinfunction "3_3") (pintype "passive"))
      (node (ref "LED") (pin "A") (pinfunction "A_A") (pintype "passive"))
      (node (ref "R2") (pin "P$1") (pinfunction "1_P$1") (pintype "passive"))
    )
    (net (code "71") (name "Net-(R2-2)") (class "Default")
      (node (ref "HEADERPIN") (pin "2") (pinfunction "2_2") (pintype "passive"))
      (node (ref "LDR") (pin "A") (pinfunction "A_A") (pintype "passive"))
      (node (ref "R2") (pin "P$2") (pinfunction "2_P$2") (pintype "passive"))
    )
    (net (code "72") (name "Net-(R4-1)") (class "Default")
      (node (ref "HEADERPIN1") (pin "3") (pinfunction "3_3") (pintype "passive"))
      (node (ref "LED5") (pin "A") (pinfunction "A_A") (pintype "passive"))
      (node (ref "R4") (pin "P$1") (pinfunction "1_P$1") (pintype "passive"))
    )
    (net (code "73") (name "Net-(R4-2)") (class "Default")
      (node (ref "HEADERPIN1") (pin "2") (pinfunction "2_2") (pintype "passive"))
      (node (ref "LDR1") (pin "A") (pinfunction "A_A") (pintype "passive"))
      (node (ref "R4") (pin "P$2") (pinfunction "2_P$2") (pintype "passive"))
    )
    (net (code "74") (name "Net-(R6-1)") (class "Default")
      (node (ref "HEADERPIN2") (pin "3") (pinfunction "3_3") (pintype "passive"))
      (node (ref "LED6") (pin "A") (pinfunction "A_A") (pintype "passive"))
      (node (ref "R6") (pin "P$1") (pinfunction "1_P$1") (pintype "passive"))
    )
    (net (code "75") (name "Net-(R6-2)") (class "Default")
      (node (ref "HEADERPIN2") (pin "2") (pinfunction "2_2") (pintype "passive"))
      (node (ref "LDR2") (pin "A") (pinfunction "A_A") (pintype "passive"))
      (node (ref "R6") (pin "P$2") (pinfunction "2_P$2") (pintype "passive"))
    )
    (net (code "76") (name "Net-(R8-1)") (class "Default")
      (node (ref "HEADERPIN3") (pin "3") (pinfunction "3_3") (pintype "passive"))
      (node (ref "LED7") (pin "A") (pinfunction "A_A") (pintype "passive"))
      (node (ref "R8") (pin "P$1") (pinfunction "1_P$1") (pintype "passive"))
    )
    (net (code "77") (name "Net-(R8-2)") (class "Default")
      (node (ref "HEADERPIN3") (pin "2") (pinfunction "2_2") (pintype "passive"))
      (node (ref "LDR3") (pin "A") (pinfunction "A_A") (pintype "passive"))
      (node (ref "R8") (pin "P$2") (pinfunction "2_P$2") (pintype "passive"))
    )
    (net (code "78") (name "Net-(R10-1)") (class "Default")
      (node (ref "HEADERPIN4") (pin "3") (pinfunction "3_3") (pintype "passive"))
      (node (ref "LED8") (pin "A") (pinfunction "A_A") (pintype "passive"))
      (node (ref "R10") (pin "P$1") (pinfunction "1_P$1") (pintype "passive"))
    )
    (net (code "79") (name "Net-(R10-2)") (class "Default")
      (node (ref "HEADERPIN4") (pin "2") (pinfunction "2_2") (pintype "passive"))
      (node (ref "LDR4") (pin "A") (pinfunction "A_A") (pintype "passive"))
      (node (ref "R10") (pin "P$2") (pinfunction "2_P$2") (pintype "passive"))
    )
    (net (code "80") (name "Net-(R12-1)") (class "Default")
      (node (ref "HEADERPIN5") (pin "3") (pinfunction "3_3") (pintype "passive"))
      (node (ref "LED9") (pin "A") (pinfunction "A_A") (pintype "passive"))
      (node (ref "R12") (pin "P$1") (pinfunction "1_P$1") (pintype "passive"))
    )
    (net (code "81") (name "Net-(R12-2)") (class "Default")
      (node (ref "HEADERPIN5") (pin "2") (pinfunction "2_2") (pintype "passive"))
      (node (ref "LDR5") (pin "A") (pinfunction "A_A") (pintype "passive"))
      (node (ref "R12") (pin "P$2") (pinfunction "2_P$2") (pintype "passive"))
    )
    (net (code "82") (name "Net-(R14-1)") (class "Default")
      (node (ref "HEADERPIN6") (pin "3") (pinfunction "3_3") (pintype "passive"))
      (node (ref "LED10") (pin "A") (pinfunction "A_A") (pintype "passive"))
      (node (ref "R14") (pin "P$1") (pinfunction "1_P$1") (pintype "passive"))
    )
    (net (code "83") (name "Net-(R14-2)") (class "Default")
      (node (ref "HEADERPIN6") (pin "2") (pinfunction "2_2") (pintype "passive"))
      (node (ref "LDR6") (pin "A") (pinfunction "A_A") (pintype "passive"))
      (node (ref "R14") (pin "P$2") (pinfunction "2_P$2") (pintype "passive"))
    )
    (net (code "84") (name "Net-(R16-1)") (class "Default")
      (node (ref "HEADERPIN7") (pin "3") (pinfunction "3_3") (pintype "passive"))
      (node (ref "LED11") (pin "A") (pinfunction "A_A") (pintype "passive"))
      (node (ref "R16") (pin "P$1") (pinfunction "1_P$1") (pintype "passive"))
    )
    (net (code "85") (name "Net-(R16-2)") (class "Default")
      (node (ref "HEADERPIN7") (pin "2") (pinfunction "2_2") (pintype "passive"))
      (node (ref "LDR7") (pin "A") (pinfunction "A_A") (pintype "passive"))
      (node (ref "R16") (pin "P$2") (pinfunction "2_P$2") (pintype "passive"))
    )
    (net (code "86") (name "Net-(R18-1)") (class "Default")
      (node (ref "HEADERPIN8") (pin "3") (pinfunction "3_3") (pintype "passive"))
      (node (ref "LED12") (pin "A") (pinfunction "A_A") (pintype "passive"))
      (node (ref "R18") (pin "P$1") (pinfunction "1_P$1") (pintype "passive"))
    )
    (net (code "87") (name "Net-(R18-2)") (class "Default")
      (node (ref "HEADERPIN8") (pin "2") (pinfunction "2_2") (pintype "passive"))
      (node (ref "LDR8") (pin "A") (pinfunction "A_A") (pintype "passive"))
      (node (ref "R18") (pin "P$2") (pinfunction "2_P$2") (pintype "passive"))
    )
    (net (code "88") (name "PWM3") (class "Default")
      (node (ref "PONTE-H-DIREITA") (pin "3") (pinfunction "3_3") (pintype "passive"))
      (node (ref "U1") (pin "3") (pinfunction "3_3") (pintype "bidirectional"))
    )
    (net (code "89") (name "PWM4") (class "Default")
      (node (ref "PONTE-H-DIREITA") (pin "4") (pinfunction "4_4") (pintype "passive"))
      (node (ref "U1") (pin "4") (pinfunction "4_4") (pintype "bidirectional"))
    )
    (net (code "90") (name "PWM5") (class "Default")
      (node (ref "PONTE-H-DIREITA") (pin "6") (pinfunction "6_6") (pintype "passive"))
      (node (ref "U1") (pin "5") (pinfunction "5_5") (pintype "bidirectional"))
    )
    (net (code "91") (name "PWM6") (class "Default")
      (node (ref "PONTE-H-DIREITA") (pin "7") (pinfunction "7_7") (pintype "passive"))
      (node (ref "U1") (pin "6") (pinfunction "6_6") (pintype "bidirectional"))
    )
    (net (code "92") (name "PWM7") (class "Default")
      (node (ref "U1") (pin "7") (pinfunction "7_7") (pintype "bidirectional"))
    )
    (net (code "93") (name "PWM8") (class "Default")
      (node (ref "SERVO3") (pin "3") (pinfunction "3_3") (pintype "passive"))
      (node (ref "U1") (pin "8") (pinfunction "8_8") (pintype "bidirectional"))
    )
    (net (code "94") (name "PWM9") (class "Default")
      (node (ref "SERVO4") (pin "3") (pinfunction "3_3") (pintype "passive"))
      (node (ref "U1") (pin "9") (pinfunction "9_9") (pintype "bidirectional"))
    )
    (net (code "95") (name "PWM10") (class "Default")
      (node (ref "SERVO1") (pin "3") (pinfunction "3_3") (pintype "passive"))
      (node (ref "U1") (pin "10") (pinfunction "10_10") (pintype "bidirectional"))
    )
    (net (code "96") (name "PWM11") (class "Default")
      (node (ref "SERVO2") (pin "3") (pinfunction "3_3") (pintype "passive"))
      (node (ref "U1") (pin "11") (pinfunction "11_11") (pintype "bidirectional"))
    )
    (net (code "97") (name "PWM12") (class "Default")
      (node (ref "K1") (pin "1") (pinfunction "1_1") (pintype "passive"))
      (node (ref "U1") (pin "12") (pinfunction "12_12") (pintype "bidirectional"))
    )
    (net (code "98") (name "SCL") (class "Default")
      (node (ref "U1") (pin "21") (pinfunction "21(SCL)_21") (pintype "bidirectional"))
      (node (ref "U2") (pin "SCL") (pinfunction "SCL_SCL") (pintype "bidirectional"))
    )
    (net (code "99") (name "SDA") (class "Default")
      (node (ref "U1") (pin "20") (pinfunction "20(SDA)_20") (pintype "bidirectional"))
      (node (ref "U2") (pin "SDA") (pinfunction "SDA_SDA") (pintype "bidirectional"))
    )
    (net (code "100") (name "VCC") (class "Default")
      (node (ref "22K") (pin "P$1") (pinfunction "1_P$1") (pintype "passive"))
      (node (ref "J2") (pin "1") (pinfunction "1_1") (pintype "passive"))
      (node (ref "K1") (pin "P") (pinfunction "P_P") (pintype "passive"))
      (node (ref "LM7805A") (pin "1") (pinfunction "VI_1") (pintype "input"))
      (node (ref "LM7805B") (pin "1") (pinfunction "VI_1") (pintype "input"))
      (node (ref "LM7805C") (pin "1") (pinfunction "VI_1") (pintype "input"))
      (node (ref "PONTE-H-ESQUERDA") (pin "7") (pinfunction "7_7") (pintype "passive"))
      (node (ref "U1") (pin "VIN") (pinfunction "VIN_VIN") (pintype "bidirectional"))
    )
    (net (code "101") (name "unconnected-(ARRAY-Pad9)") (class "Default")
      (node (ref "ARRAY") (pin "9") (pinfunction "9_9") (pintype "passive"))
    )
    (net (code "102") (name "unconnected-(K1-PadS)") (class "Default")
      (node (ref "K1") (pin "S") (pinfunction "S_S") (pintype "passive"))
    )
    (net (code "103") (name "unconnected-(U1-0(RX0)-Pad0)") (class "Default")
      (node (ref "U1") (pin "0") (pinfunction "0(RX0)_0") (pintype "bidirectional"))
    )
    (net (code "104") (name "unconnected-(U1-1(TX0)-Pad1)") (class "Default")
      (node (ref "U1") (pin "1") (pinfunction "1(TX0)_1") (pintype "bidirectional"))
    )
    (net (code "105") (name "unconnected-(U1-5V-Pad5V@0)") (class "Default")
      (node (ref "U1") (pin "5V@0") (pinfunction "5V_5V@0") (pintype "bidirectional"))
    )
    (net (code "106") (name "unconnected-(U1-5V-Pad5V@1)") (class "Default")
      (node (ref "U1") (pin "5V@1") (pinfunction "5V_5V@1") (pintype "bidirectional"))
    )
    (net (code "107") (name "unconnected-(U1-5V-Pad5V@2)") (class "Default")
      (node (ref "U1") (pin "5V@2") (pinfunction "5V_5V@2") (pintype "bidirectional"))
    )
    (net (code "108") (name "unconnected-(U1-14(TX3)-Pad14)") (class "Default")
      (node (ref "U1") (pin "14") (pinfunction "14(TX3)_14") (pintype "bidirectional"))
    )
    (net (code "109") (name "unconnected-(U1-15(RX3)-Pad15)") (class "Default")
      (node (ref "U1") (pin "15") (pinfunction "15(RX3)_15") (pintype "bidirectional"))
    )
    (net (code "110") (name "unconnected-(U1-16(TX2)-Pad16)") (class "Default")
      (node (ref "U1") (pin "16") (pinfunction "16(TX2)_16") (pintype "bidirectional"))
    )
    (net (code "111") (name "unconnected-(U1-17(RX2)-Pad17)") (class "Default")
      (node (ref "U1") (pin "17") (pinfunction "17(RX2)_17") (pintype "bidirectional"))
    )
    (net (code "112") (name "unconnected-(U1-18(TX1)-Pad18)") (class "Default")
      (node (ref "U1") (pin "18") (pinfunction "18(TX1)_18") (pintype "bidirectional"))
    )
    (net (code "113") (name "unconnected-(U1-19(RX1)-Pad19)") (class "Default")
      (node (ref "U1") (pin "19") (pinfunction "19(RX1)_19") (pintype "bidirectional"))
    )
    (net (code "114") (name "unconnected-(U1-Pad3.3V)") (class "Default")
      (node (ref "U1") (pin "3.3V") (pinfunction "3.3V_3.3V") (pintype "bidirectional"))
    )
    (net (code "115") (name "unconnected-(U1-Pad22)") (class "Default")
      (node (ref "U1") (pin "22") (pinfunction "22_22") (pintype "bidirectional"))
    )
    (net (code "116") (name "unconnected-(U1-Pad23)") (class "Default")
      (node (ref "U1") (pin "23") (pinfunction "23_23") (pintype "bidirectional"))
    )
    (net (code "117") (name "unconnected-(U1-Pad24)") (class "Default")
      (node (ref "U1") (pin "24") (pinfunction "24_24") (pintype "bidirectional"))
    )
    (net (code "118") (name "unconnected-(U1-Pad43)") (class "Default")
      (node (ref "U1") (pin "43") (pinfunction "43_43") (pintype "bidirectional"))
    )
    (net (code "119") (name "unconnected-(U1-Pad44)") (class "Default")
      (node (ref "U1") (pin "44") (pinfunction "44_44") (pintype "bidirectional"))
    )
    (net (code "120") (name "unconnected-(U1-Pad45)") (class "Default")
      (node (ref "U1") (pin "45") (pinfunction "45_45") (pintype "bidirectional"))
    )
    (net (code "121") (name "unconnected-(U1-Pad46)") (class "Default")
      (node (ref "U1") (pin "46") (pinfunction "46_46") (pintype "bidirectional"))
    )
    (net (code "122") (name "unconnected-(U1-Pad47)") (class "Default")
      (node (ref "U1") (pin "47") (pinfunction "47_47") (pintype "bidirectional"))
    )
    (net (code "123") (name "unconnected-(U1-Pad48)") (class "Default")
      (node (ref "U1") (pin "48") (pinfunction "48_48") (pintype "bidirectional"))
    )
    (net (code "124") (name "unconnected-(U1-Pad49)") (class "Default")
      (node (ref "U1") (pin "49") (pinfunction "49_49") (pintype "bidirectional"))
    )
    (net (code "125") (name "unconnected-(U1-Pad50)") (class "Default")
      (node (ref "U1") (pin "50") (pinfunction "50_50") (pintype "bidirectional"))
    )
    (net (code "126") (name "unconnected-(U1-Pad52)") (class "Default")
      (node (ref "U1") (pin "52") (pinfunction "52_52") (pintype "bidirectional"))
    )
    (net (code "127") (name "unconnected-(U1-PadAREF)") (class "Default")
      (node (ref "U1") (pin "AREF") (pinfunction "AREF_AREF") (pintype "bidirectional"))
    )
    (net (code "128") (name "unconnected-(U1-PadRESET)") (class "Default")
      (node (ref "U1") (pin "RESET") (pinfunction "RESET_RESET") (pintype "bidirectional"))
    )
    (net (code "129") (name "unconnected-(U2-PadADO)") (class "Default")
      (node (ref "U2") (pin "ADO") (pinfunction "ADO_ADO") (pintype "bidirectional"))
    )
    (net (code "130") (name "unconnected-(U2-PadXCL)") (class "Default")
      (node (ref "U2") (pin "XCL") (pinfunction "XCL_XCL") (pintype "bidirectional"))
    )
    (net (code "131") (name "unconnected-(U2-PadXDA)") (class "Default")
      (node (ref "U2") (pin "XDA") (pinfunction "XDA_XDA") (pintype "bidirectional"))
    )
  )
)
